# Arduino5VPowerSupply.net
KiCad netlist of a schematic drawn in EAGLE
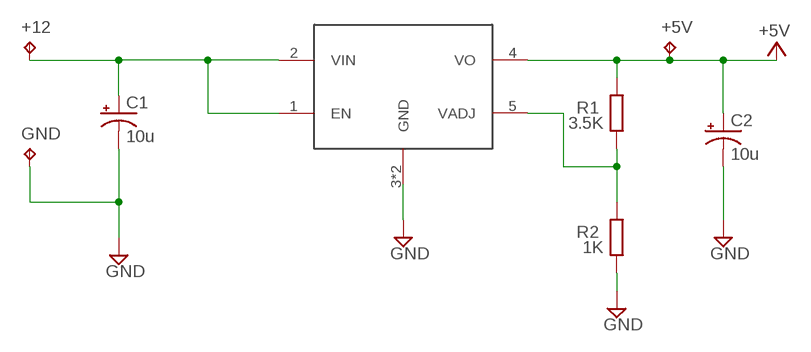
[diagram p0: schematic, sheet 1]

(export (version "E")
  (design (tool "Eeschema 10.0.6"))
  (components
    (comp (ref "+5V")
      (value "TPPAD1-13")
      (footprint "eagle-import:P1-13")
      (libsource (lib "eagle-import") (part "TPPAD1-13"))
    )
    (comp (ref "+12")
      (value "TPPAD1-13")
      (footprint "eagle-import:P1-13")
      (libsource (lib "eagle-import") (part "TPPAD1-13"))
    )
    (comp (ref "C1")
      (value "10u")
      (footprint "eagle-import:153CLV-0405")
      (libsource (lib "eagle-import") (part "CPOL-US153CLV-0405"))
    )
    (comp (ref "C2")
      (value "10u")
      (footprint "eagle-import:153CLV-0405")
      (libsource (lib "eagle-import") (part "CPOL-US153CLV-0405"))
    )
    (comp (ref "GND")
      (value "TPPAD1-13")
      (footprint "eagle-import:P1-13")
      (libsource (lib "eagle-import") (part "TPPAD1-13"))
    )
    (comp (ref "R1")
      (value "3.5K")
      (footprint "eagle-import:R0805")
      (libsource (lib "eagle-import") (part "R-EU_R0805"))
    )
    (comp (ref "R2")
      (value "1K")
      (footprint "eagle-import:R0805")
      (libsource (lib "eagle-import") (part "R-EU_R0805"))
    )
    (comp (ref "U5")
      (value "TLF1963TBATMA1")
      (footprint "eagle-import:DPAK")
      (libsource (lib "eagle-import") (part "TLF1963"))
    )
  )
  (nets
    (net (code "1") (name "+5V") (class "Default")
      (node (ref "+5V") (pin "TP") (pinfunction "TP_TP") (pintype "input"))
      (node (ref "C2") (pin "+") (pinfunction "+_+") (pintype "passive"))
      (node (ref "R1") (pin "2") (pinfunction "2_2") (pintype "passive"))
      (node (ref "U5") (pin "4") (pinfunction "VO_4") (pintype "bidirectional"))
    )
    (net (code "2") (name "GND") (class "Default")
      (node (ref "C1") (pin "-") (pinfunction "-_-") (pintype "passive"))
      (node (ref "C2") (pin "-") (pinfunction "-_-") (pintype "passive"))
      (node (ref "GND") (pin "TP") (pinfunction "TP_TP") (pintype "input"))
      (node (ref "R2") (pin "1") (pinfunction "1_1") (pintype "passive"))
      (node (ref "U5") (pin "3") (pinfunction "GND_3") (pintype "bidirectional"))
      (node (ref "U5") (pin "6") (pinfunction "GND_6") (pintype "bidirectional"))
    )
    (net (code "3") (name "Net-(U5-EN)") (class "Default")
      (node (ref "+12") (pin "TP") (pinfunction "TP_TP") (pintype "input"))
      (node (ref "C1") (pin "+") (pinfunction "+_+") (pintype "passive"))
      (node (ref "U5") (pin "1") (pinfunction "EN_1") (pintype "bidirectional"))
      (node (ref "U5") (pin "2") (pinfunction "VIN_2") (pintype "bidirectional"))
    )
    (net (code "4") (name "Net-(U5-VADJ)") (class "Default")
      (node (ref "R1") (pin "1") (pinfunction "1_1") (pintype "passive"))
      (node (ref "R2") (pin "2") (pinfunction "2_2") (pintype "passive"))
      (node (ref "U5") (pin "5") (pinfunction "VADJ_5") (pintype "bidirectional"))
    )
  )
)
